# board.net
KiCad netlist of a schematic drawn in EAGLE
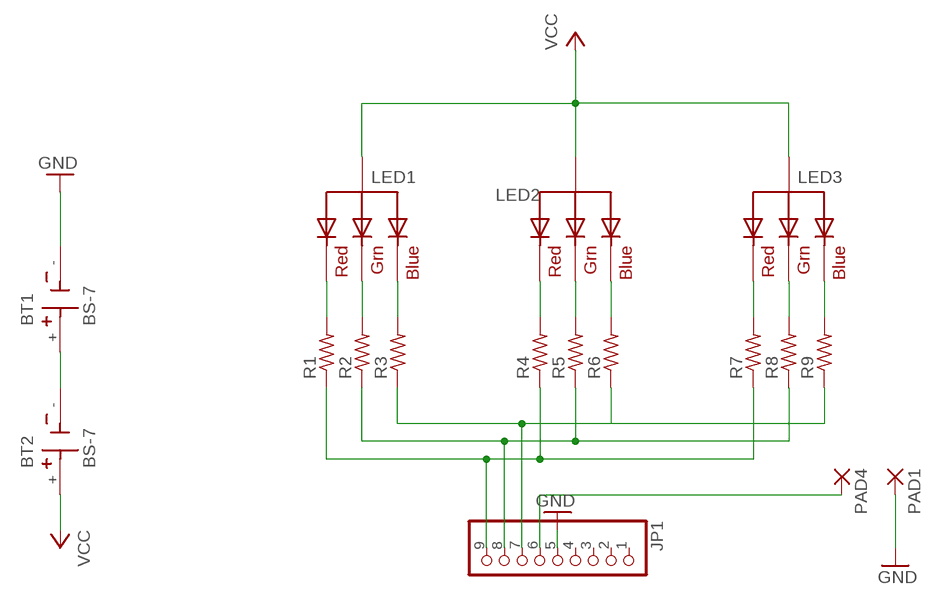
[diagram p0: schematic, sheet 1]

(export (version "E")
  (design (tool "Eeschema 10.0.6"))
  (components
    (comp (ref "BT1")
      (value "BS-7")
      (footprint "eagle-import:BAT_BS-7")
      (fields (field (name "MF") "MPD (Memory"))
      (libsource (lib "eagle-import") (part "BS-7"))
    )
    (comp (ref "BT2")
      (value "BS-7")
      (footprint "eagle-import:BAT_BS-7")
      (fields (field (name "MF") "MPD (Memory"))
      (libsource (lib "eagle-import") (part "BS-7"))
    )
    (comp (ref "JP1")
      (value "PINHD-1X9")
      (footprint "eagle-import:1X09-BIG")
      (libsource (lib "eagle-import") (part "PINHD-1X9"))
    )
    (comp (ref "LED1")
      (value "RGBLED_CA-5MM")
      (footprint "eagle-import:LED5MMRGB")
      (libsource (lib "eagle-import") (part "RGBLED_CA-5MM"))
    )
    (comp (ref "LED2")
      (value "RGBLED_CA-5MM")
      (footprint "eagle-import:LED5MMRGB")
      (libsource (lib "eagle-import") (part "RGBLED_CA-5MM"))
    )
    (comp (ref "LED3")
      (value "RGBLED_CA-5MM")
      (footprint "eagle-import:LED5MMRGB")
      (libsource (lib "eagle-import") (part "RGBLED_CA-5MM"))
    )
    (comp (ref "PAD1")
      (value "1,6/0,8")
      (footprint "eagle-import:1,6_0,8")
      (libsource (lib "eagle-import") (part "1,6/0,8"))
    )
    (comp (ref "PAD4")
      (value "1,6/0,8")
      (footprint "eagle-import:1,6_0,8")
      (libsource (lib "eagle-import") (part "1,6/0,8"))
    )
    (comp (ref "R1")
      (value "R-US_0207/7")
      (footprint "eagle-import:0207_7")
      (libsource (lib "eagle-import") (part "R-US_0207/7"))
    )
    (comp (ref "R2")
      (value "R-US_0207/7")
      (footprint "eagle-import:0207_7")
      (libsource (lib "eagle-import") (part "R-US_0207/7"))
    )
    (comp (ref "R3")
      (value "R-US_0207/7")
      (footprint "eagle-import:0207_7")
      (libsource (lib "eagle-import") (part "R-US_0207/7"))
    )
    (comp (ref "R4")
      (value "R-US_0207/7")
      (footprint "eagle-import:0207_7")
      (libsource (lib "eagle-import") (part "R-US_0207/7"))
    )
    (comp (ref "R5")
      (value "R-US_0207/7")
      (footprint "eagle-import:0207_7")
      (libsource (lib "eagle-import") (part "R-US_0207/7"))
    )
    (comp (ref "R6")
      (value "R-US_0207/7")
      (footprint "eagle-import:0207_7")
      (libsource (lib "eagle-import") (part "R-US_0207/7"))
    )
    (comp (ref "R7")
      (value "R-US_0207/7")
      (footprint "eagle-import:0207_7")
      (libsource (lib "eagle-import") (part "R-US_0207/7"))
    )
    (comp (ref "R8")
      (value "R-US_0207/7")
      (footprint "eagle-import:0207_7")
      (libsource (lib "eagle-import") (part "R-US_0207/7"))
    )
    (comp (ref "R9")
      (value "R-US_0207/7")
      (footprint "eagle-import:0207_7")
      (libsource (lib "eagle-import") (part "R-US_0207/7"))
    )
  )
  (nets
    (net (code "1") (name "GND") (class "Default")
      (node (ref "BT1") (pin "-") (pinfunction "-_-") (pintype "passive"))
      (node (ref "JP1") (pin "5") (pinfunction "5_5") (pintype "passive"))
      (node (ref "PAD1") (pin "1") (pinfunction "P_1") (pintype "passive"))
    )
    (net (code "2") (name "Net-(BT1-Pad+)") (class "Default")
      (node (ref "BT1") (pin "+") (pinfunction "+_+") (pintype "passive"))
      (node (ref "BT2") (pin "-") (pinfunction "-_-") (pintype "passive"))
    )
    (net (code "3") (name "Net-(JP1-Pad7)") (class "Default")
      (node (ref "JP1") (pin "7") (pinfunction "7_7") (pintype "passive"))
      (node (ref "R3") (pin "1") (pinfunction "1_1") (pintype "passive"))
      (node (ref "R6") (pin "1") (pinfunction "1_1") (pintype "passive"))
      (node (ref "R9") (pin "1") (pinfunction "1_1") (pintype "passive"))
    )
    (net (code "4") (name "Net-(JP1-Pad8)") (class "Default")
      (node (ref "JP1") (pin "8") (pinfunction "8_8") (pintype "passive"))
      (node (ref "R2") (pin "1") (pinfunction "1_1") (pintype "passive"))
      (node (ref "R5") (pin "1") (pinfunction "1_1") (pintype "passive"))
      (node (ref "R8") (pin "1") (pinfunction "1_1") (pintype "passive"))
    )
    (net (code "5") (name "Net-(JP1-Pad9)") (class "Default")
      (node (ref "JP1") (pin "9") (pinfunction "9_9") (pintype "passive"))
      (node (ref "R1") (pin "1") (pinfunction "1_1") (pintype "passive"))
      (node (ref "R4") (pin "1") (pinfunction "1_1") (pintype "passive"))
      (node (ref "R7") (pin "1") (pinfunction "1_1") (pintype "passive"))
    )
    (net (code "6") (name "Net-(LED1-BLUE)") (class "Default")
      (node (ref "LED1") (pin "4") (pinfunction "BLUE_4") (pintype "bidirectional"))
      (node (ref "R3") (pin "2") (pinfunction "2_2") (pintype "passive"))
    )
    (net (code "7") (name "Net-(LED1-GREEN)") (class "Default")
      (node (ref "LED1") (pin "3") (pinfunction "GREEN_3") (pintype "bidirectional"))
      (node (ref "R2") (pin "2") (pinfunction "2_2") (pintype "passive"))
    )
    (net (code "8") (name "Net-(LED1-RED)") (class "Default")
      (node (ref "LED1") (pin "1") (pinfunction "RED_1") (pintype "bidirectional"))
      (node (ref "R1") (pin "2") (pinfunction "2_2") (pintype "passive"))
    )
    (net (code "9") (name "Net-(LED2-BLUE)") (class "Default")
      (node (ref "LED2") (pin "4") (pinfunction "BLUE_4") (pintype "bidirectional"))
      (node (ref "R6") (pin "2") (pinfunction "2_2") (pintype "passive"))
    )
    (net (code "10") (name "Net-(LED2-GREEN)") (class "Default")
      (node (ref "LED2") (pin "3") (pinfunction "GREEN_3") (pintype "bidirectional"))
      (node (ref "R5") (pin "2") (pinfunction "2_2") (pintype "passive"))
    )
    (net (code "11") (name "Net-(LED2-RED)") (class "Default")
      (node (ref "LED2") (pin "1") (pinfunction "RED_1") (pintype "bidirectional"))
      (node (ref "R4") (pin "2") (pinfunction "2_2") (pintype "passive"))
    )
    (net (code "12") (name "Net-(LED3-BLUE)") (class "Default")
      (node (ref "LED3") (pin "4") (pinfunction "BLUE_4") (pintype "bidirectional"))
      (node (ref "R9") (pin "2") (pinfunction "2_2") (pintype "passive"))
    )
    (net (code "13") (name "Net-(LED3-GREEN)") (class "Default")
      (node (ref "LED3") (pin "3") (pinfunction "GREEN_3") (pintype "bidirectional"))
      (node (ref "R8") (pin "2") (pinfunction "2_2") (pintype "passive"))
    )
    (net (code "14") (name "Net-(LED3-RED)") (class "Default")
      (node (ref "LED3") (pin "1") (pinfunction "RED_1") (pintype "bidirectional"))
      (node (ref "R7") (pin "2") (pinfunction "2_2") (pintype "passive"))
    )
    (net (code "15") (name "Net-(PAD4-P)") (class "Default")
      (node (ref "JP1") (pin "6") (pinfunction "6_6") (pintype "passive"))
      (node (ref "PAD4") (pin "1") (pinfunction "P_1") (pintype "passive"))
    )
    (net (code "16") (name "VCC") (class "Default")
      (node (ref "BT2") (pin "+") (pinfunction "+_+") (pintype "passive"))
      (node (ref "LED1") (pin "2") (pinfunction "VCC_2") (pintype "bidirectional"))
      (node (ref "LED2") (pin "2") (pinfunction "VCC_2") (pintype "bidirectional"))
      (node (ref "LED3") (pin "2") (pinfunction "VCC_2") (pintype "bidirectional"))
    )
    (net (code "17") (name "unconnected-(JP1-Pad1)") (class "Default")
      (node (ref "JP1") (pin "1") (pinfunction "1_1") (pintype "passive"))
    )
    (net (code "18") (name "unconnected-(JP1-Pad2)") (class "Default")
      (node (ref "JP1") (pin "2") (pinfunction "2_2") (pintype "passive"))
    )
    (net (code "19") (name "unconnected-(JP1-Pad3)") (class "Default")
      (node (ref "JP1") (pin "3") (pinfunction "3_3") (pintype "passive"))
    )
    (net (code "20") (name "unconnected-(JP1-Pad4)") (class "Default")
      (node (ref "JP1") (pin "4") (pinfunction "4_4") (pintype "passive"))
    )
  )
)
